# Indication.net
KiCad netlist of a schematic drawn in Altium Designer
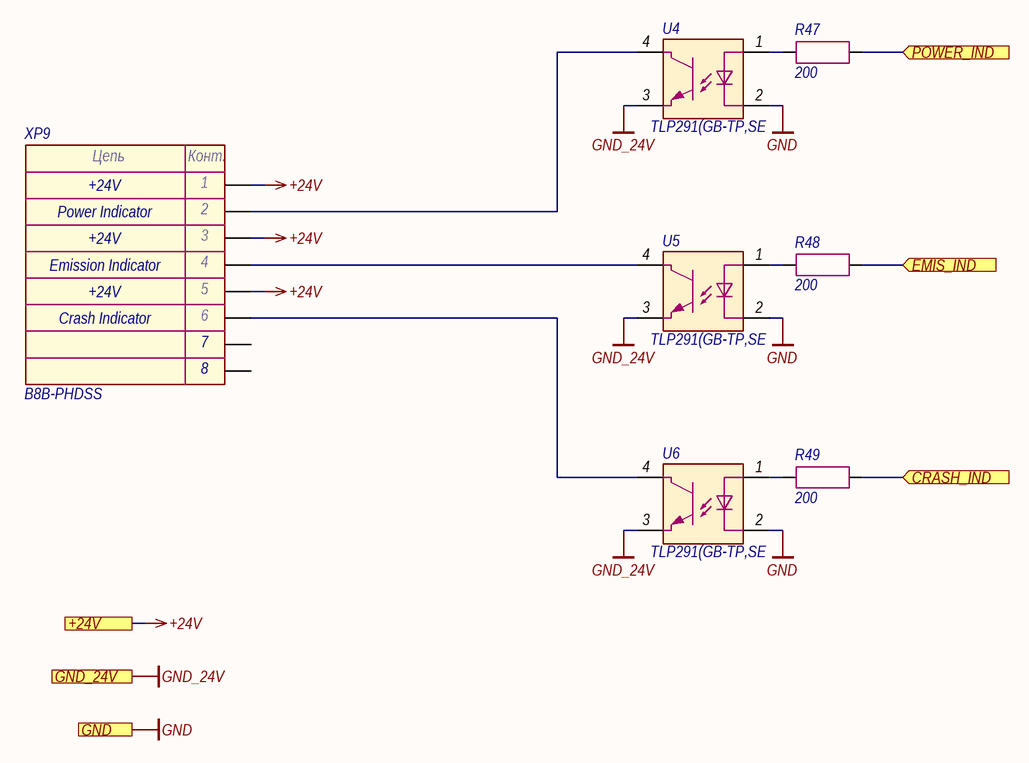
[diagram p0: Indication.SchDoc]

(export (version "E")
  (design (tool "Eeschema 10.0.6"))
  (components
    (comp (ref "R47")
      (value "200")
      (footprint "Pcb_library:RES_0603")
      (fields (field (name "MANUFACTURER") "Yageo"))
      (libsource (lib "Schem_library") (part "Resistor"))
    )
    (comp (ref "R48")
      (value "200")
      (footprint "Pcb_library:RES_0603")
      (fields (field (name "MANUFACTURER") "Yageo"))
      (libsource (lib "Schem_library") (part "Resistor"))
    )
    (comp (ref "R49")
      (value "200")
      (footprint "Pcb_library:RES_0603")
      (fields (field (name "MANUFACTURER") "Yageo"))
      (libsource (lib "Schem_library") (part "Resistor"))
    )
    (comp (ref "U4")
      (value "TLP291(GB-TP,SE")
      (footprint "Pcb_library:11-3C1")
      (fields (field (name "MANUFACTURER") "Toshiba"))
      (libsource (lib "Schem_library") (part "TLP291"))
    )
    (comp (ref "U5")
      (value "TLP291(GB-TP,SE")
      (footprint "Pcb_library:11-3C1")
      (fields (field (name "MANUFACTURER") "Toshiba"))
      (libsource (lib "Schem_library") (part "TLP291"))
    )
    (comp (ref "U6")
      (value "TLP291(GB-TP,SE")
      (footprint "Pcb_library:11-3C1")
      (fields (field (name "MANUFACTURER") "Toshiba"))
      (libsource (lib "Schem_library") (part "TLP291"))
    )
    (comp (ref "XP9")
      (value "B8B-PHDSS")
      (footprint "Pcb_library:B8B-PHDSS")
      (fields (field (name "MANUFACTURER") "JST"))
      (libsource (lib "Schem_library") (part "Connector-8"))
    )
  )
  (nets
    (net (code "1") (name "+24V") (class "Default")
      (node (ref "XP9") (pin "1") (pintype "passive"))
      (node (ref "XP9") (pin "3") (pintype "passive"))
      (node (ref "XP9") (pin "5") (pintype "passive"))
    )
    (net (code "2") (name "/CRASH_IND") (class "Default")
      (node (ref "R49") (pin "2") (pinfunction "2_2") (pintype "passive"))
    )
    (net (code "3") (name "/EMIS_IND") (class "Default")
      (node (ref "R48") (pin "2") (pinfunction "2_2") (pintype "passive"))
    )
    (net (code "4") (name "/POWER_IND") (class "Default")
      (node (ref "R47") (pin "2") (pinfunction "2_2") (pintype "passive"))
    )
    (net (code "5") (name "GND") (class "Default")
      (node (ref "U4") (pin "2") (pintype "passive"))
      (node (ref "U5") (pin "2") (pintype "passive"))
      (node (ref "U6") (pin "2") (pintype "passive"))
    )
    (net (code "6") (name "GND_24V") (class "Default")
      (node (ref "U4") (pin "3") (pintype "passive"))
      (node (ref "U5") (pin "3") (pintype "passive"))
      (node (ref "U6") (pin "3") (pintype "passive"))
    )
    (net (code "7") (name "Net-(R47-Pad1)") (class "Default")
      (node (ref "R47") (pin "1") (pinfunction "1_1") (pintype "passive"))
      (node (ref "U4") (pin "1") (pintype "passive"))
    )
    (net (code "8") (name "Net-(R48-Pad1)") (class "Default")
      (node (ref "R48") (pin "1") (pinfunction "1_1") (pintype "passive"))
      (node (ref "U5") (pin "1") (pintype "passive"))
    )
    (net (code "9") (name "Net-(R49-Pad1)") (class "Default")
      (node (ref "R49") (pin "1") (pinfunction "1_1") (pintype "passive"))
      (node (ref "U6") (pin "1") (pintype "passive"))
    )
    (net (code "10") (name "Net-(U4-Pad4)") (class "Default")
      (node (ref "U4") (pin "4") (pintype "passive"))
      (node (ref "XP9") (pin "2") (pintype "passive"))
    )
    (net (code "11") (name "Net-(U5-Pad4)") (class "Default")
      (node (ref "U5") (pin "4") (pintype "passive"))
      (node (ref "XP9") (pin "4") (pintype "passive"))
    )
    (net (code "12") (name "Net-(U6-Pad4)") (class "Default")
      (node (ref "U6") (pin "4") (pintype "passive"))
      (node (ref "XP9") (pin "6") (pintype "passive"))
    )
    (net (code "13") (name "unconnected-(XP9-Pad7)") (class "Default")
      (node (ref "XP9") (pin "7") (pintype "passive"))
    )
    (net (code "14") (name "unconnected-(XP9-Pad8)") (class "Default")
      (node (ref "XP9") (pin "8") (pintype "passive"))
    )
  )
)
